# BMSnew.net
KiCad netlist of a schematic drawn in EAGLE
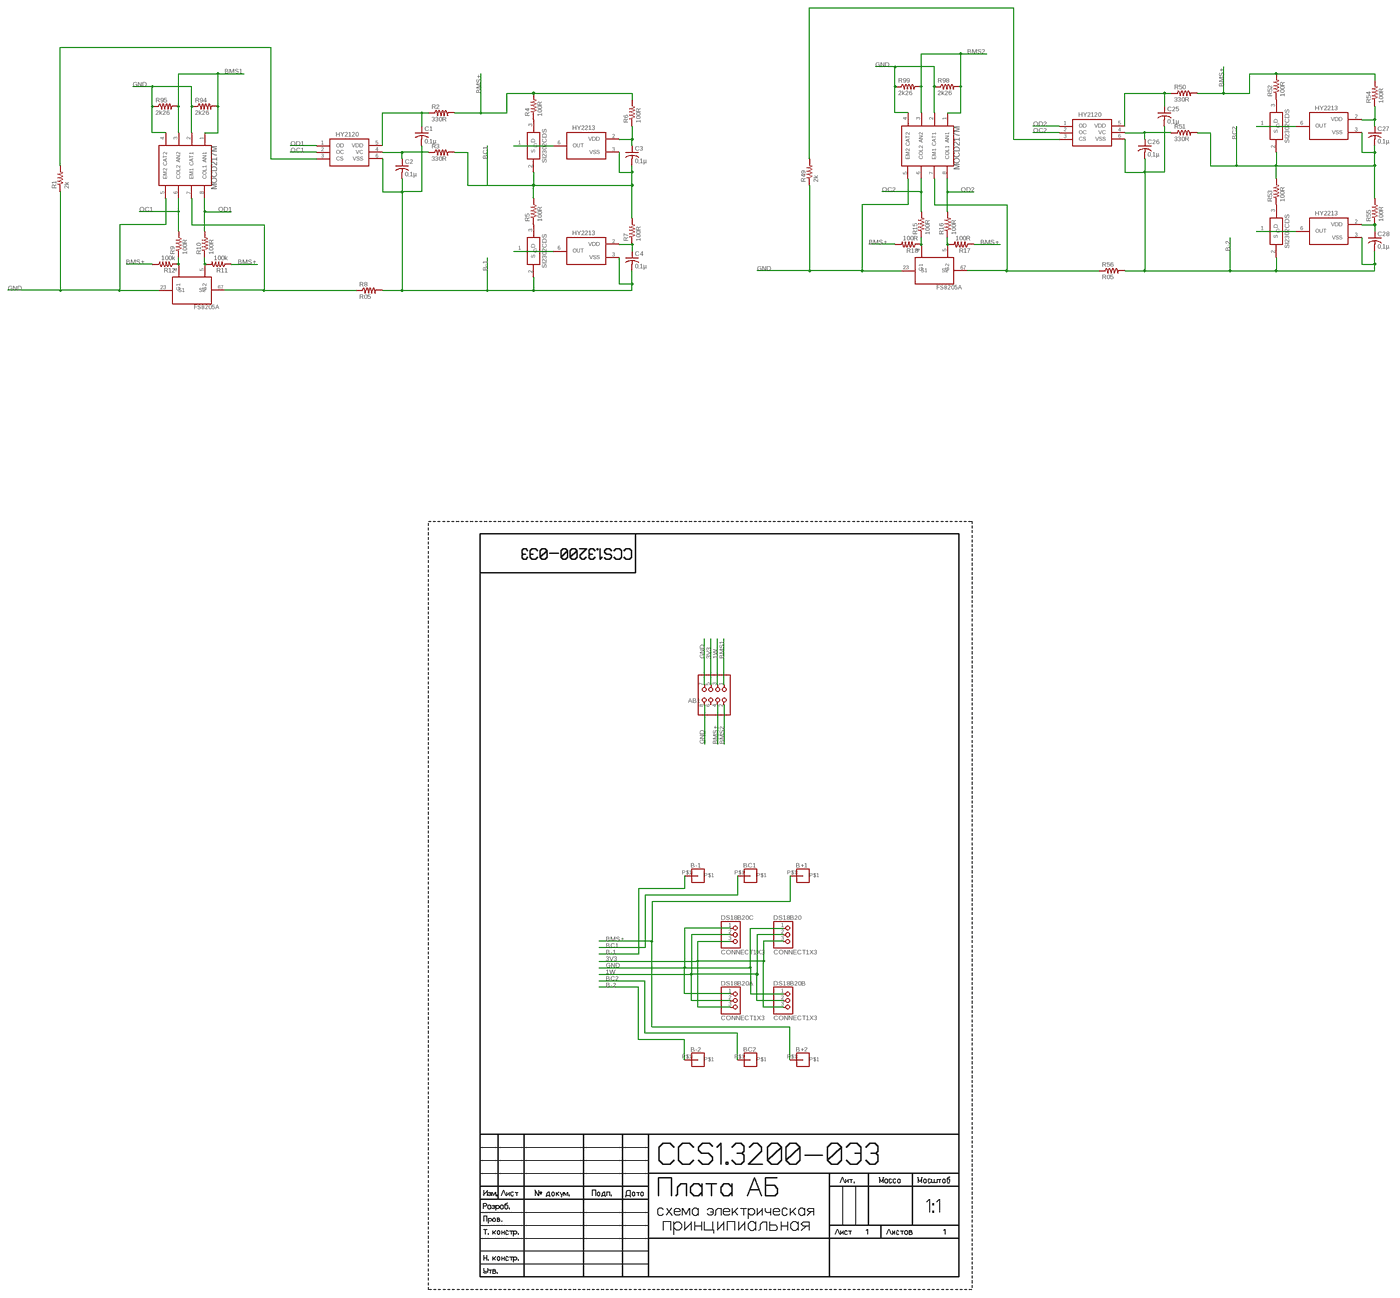
[diagram p0: schematic, sheet 1, overview]
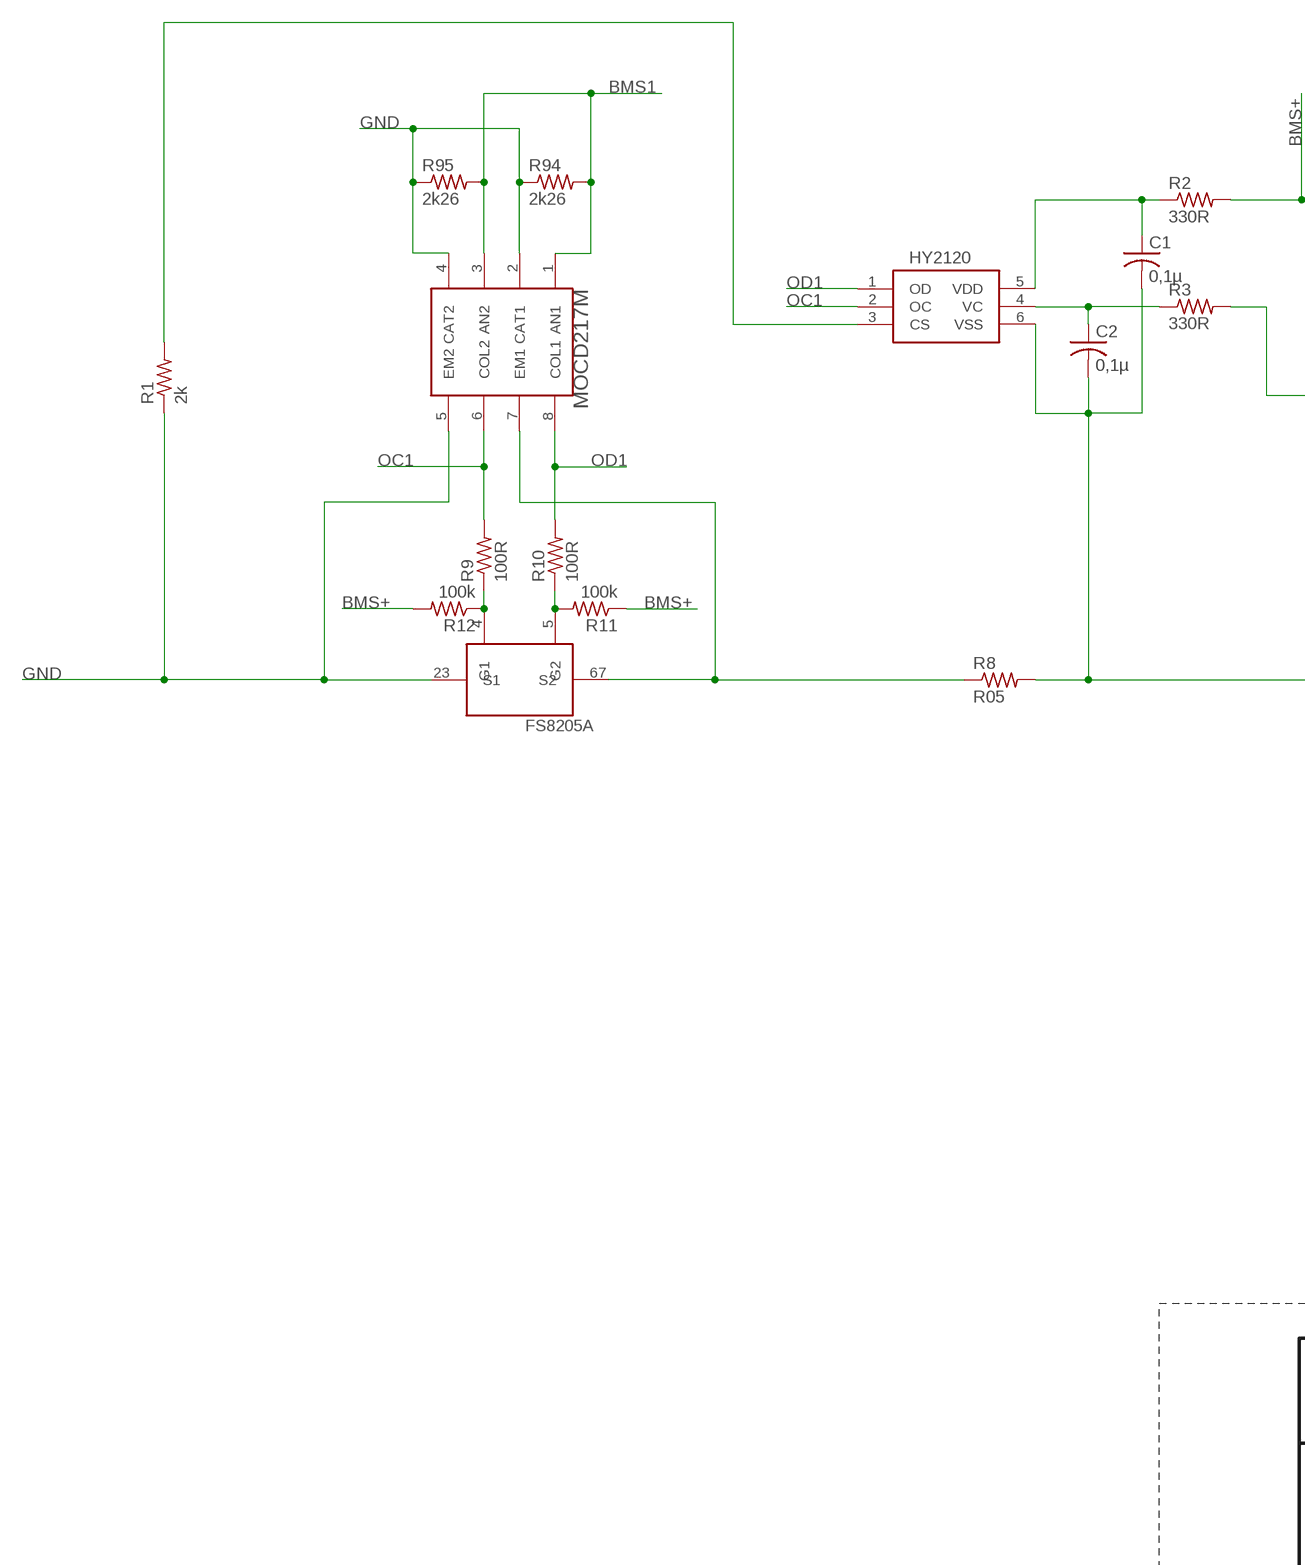
[diagram p1: schematic, sheet 1, part 1 of 4]
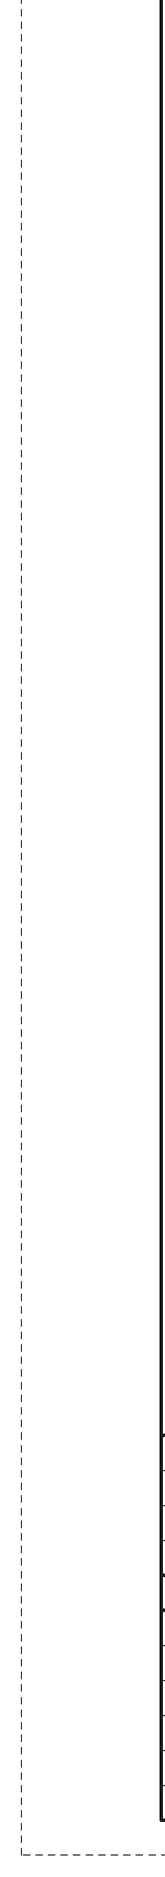
[diagram p2: schematic, sheet 1, part 2 of 4]
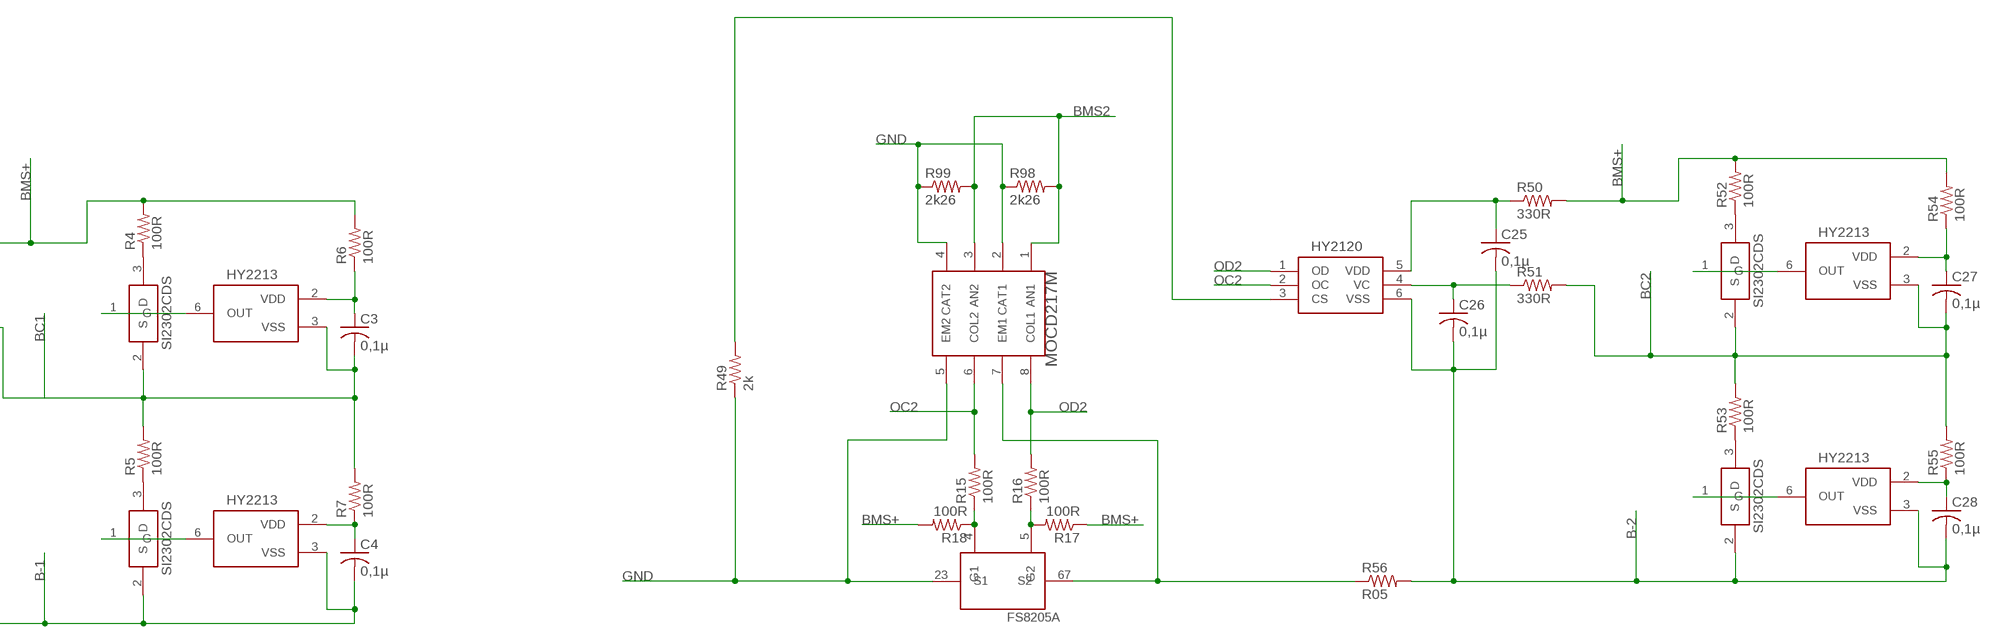
[diagram p3: schematic, sheet 1, part 3 of 4]
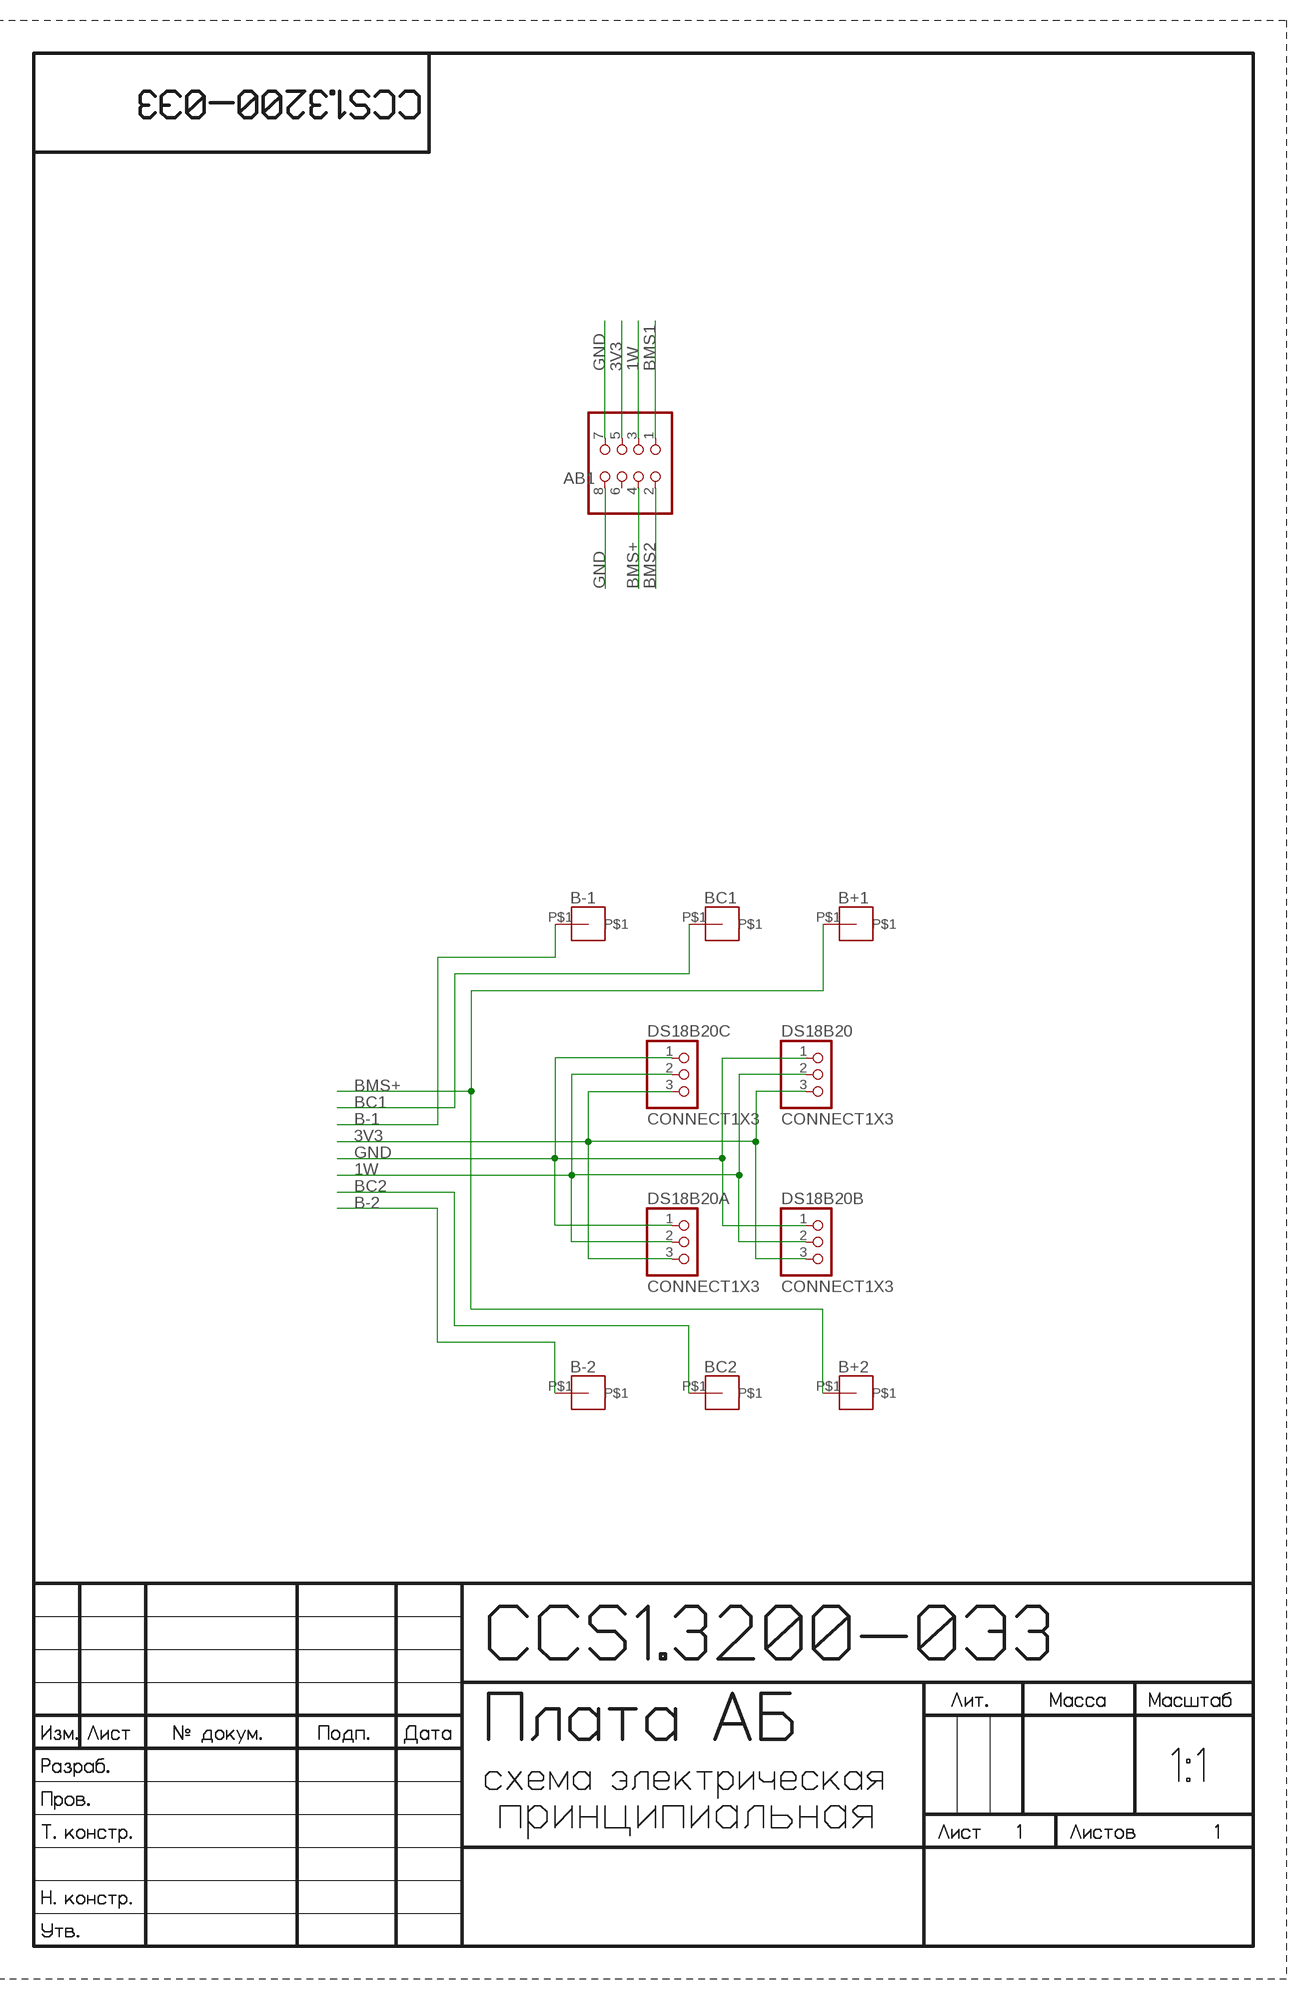
[diagram p4: schematic, sheet 1, part 4 of 4]

(export (version "E")
  (design (tool "Eeschema 10.0.6"))
  (components
    (comp (ref "AB1")
      (value "PINHD-2X4")
      (footprint "eagle-import:2X04")
      (libsource (lib "eagle-import") (part "PINHD-2X4"))
    )
    (comp (ref "B+1")
      (value "BATTERY")
      (footprint "eagle-import:BATTERY")
      (libsource (lib "eagle-import") (part "BATTERY"))
    )
    (comp (ref "B+2")
      (value "BATTERY")
      (footprint "eagle-import:BATTERY")
      (libsource (lib "eagle-import") (part "BATTERY"))
    )
    (comp (ref "B-1")
      (value "BATTERY")
      (footprint "eagle-import:BATTERY")
      (libsource (lib "eagle-import") (part "BATTERY"))
    )
    (comp (ref "B-2")
      (value "BATTERY")
      (footprint "eagle-import:BATTERY")
      (libsource (lib "eagle-import") (part "BATTERY"))
    )
    (comp (ref "BC1")
      (value "BATTERY")
      (footprint "eagle-import:BATTERY")
      (libsource (lib "eagle-import") (part "BATTERY"))
    )
    (comp (ref "BC2")
      (value "BATTERY")
      (footprint "eagle-import:BATTERY")
      (libsource (lib "eagle-import") (part "BATTERY"))
    )
    (comp (ref "C1")
      (value "0,1µ")
      (footprint "eagle-import:C0603")
      (libsource (lib "eagle-import") (part "C-USC0603"))
    )
    (comp (ref "C2")
      (value "0,1µ")
      (footprint "eagle-import:C0603")
      (libsource (lib "eagle-import") (part "C-USC0603"))
    )
    (comp (ref "C3")
      (value "0,1µ")
      (footprint "eagle-import:C0603")
      (libsource (lib "eagle-import") (part "C-USC0603"))
    )
    (comp (ref "C4")
      (value "0,1µ")
      (footprint "eagle-import:C0603")
      (libsource (lib "eagle-import") (part "C-USC0603"))
    )
    (comp (ref "C25")
      (value "0,1µ")
      (footprint "eagle-import:C0603")
      (libsource (lib "eagle-import") (part "C-USC0603"))
    )
    (comp (ref "C26")
      (value "0,1µ")
      (footprint "eagle-import:C0603")
      (libsource (lib "eagle-import") (part "C-USC0603"))
    )
    (comp (ref "C27")
      (value "0,1µ")
      (footprint "eagle-import:C0603")
      (libsource (lib "eagle-import") (part "C-USC0603"))
    )
    (comp (ref "C28")
      (value "0,1µ")
      (footprint "eagle-import:C0603")
      (libsource (lib "eagle-import") (part "C-USC0603"))
    )
    (comp (ref "DS18B20")
      (value "CONNECT1X3")
      (footprint "eagle-import:CONNECT1X3")
      (libsource (lib "eagle-import") (part "CONNECT1X3"))
    )
    (comp (ref "DS18B20A")
      (value "CONNECT1X3")
      (footprint "eagle-import:CONNECT1X3")
      (libsource (lib "eagle-import") (part "CONNECT1X3"))
    )
    (comp (ref "DS18B20B")
      (value "CONNECT1X3")
      (footprint "eagle-import:CONNECT1X3")
      (libsource (lib "eagle-import") (part "CONNECT1X3"))
    )
    (comp (ref "DS18B20C")
      (value "CONNECT1X3")
      (footprint "eagle-import:CONNECT1X3")
      (libsource (lib "eagle-import") (part "CONNECT1X3"))
    )
    (comp (ref "R1")
      (value "2k")
      (footprint "eagle-import:R0603")
      (libsource (lib "eagle-import") (part "resistor_348_R-US_R0603"))
    )
    (comp (ref "R2")
      (value "330R")
      (footprint "eagle-import:R0603")
      (libsource (lib "eagle-import") (part "resistor_348_R-US_R0603"))
    )
    (comp (ref "R3")
      (value "330R")
      (footprint "eagle-import:R0603")
      (libsource (lib "eagle-import") (part "resistor_348_R-US_R0603"))
    )
    (comp (ref "R4")
      (value "100R")
      (footprint "eagle-import:R0603")
      (libsource (lib "eagle-import") (part "resistor_348_R-US_R0603"))
    )
    (comp (ref "R5")
      (value "100R")
      (footprint "eagle-import:R0603")
      (libsource (lib "eagle-import") (part "resistor_348_R-US_R0603"))
    )
    (comp (ref "R6")
      (value "100R")
      (footprint "eagle-import:R0603")
      (libsource (lib "eagle-import") (part "resistor_348_R-US_R0603"))
    )
    (comp (ref "R7")
      (value "100R")
      (footprint "eagle-import:R0603")
      (libsource (lib "eagle-import") (part "resistor_348_R-US_R0603"))
    )
    (comp (ref "R8")
      (value "R05")
      (footprint "eagle-import:R2512")
      (libsource (lib "eagle-import") (part "R-US_R2512"))
    )
    (comp (ref "R9")
      (value "100R")
      (footprint "eagle-import:R0603")
      (libsource (lib "eagle-import") (part "resistor_348_R-US_R0603"))
    )
    (comp (ref "R10")
      (value "100R")
      (footprint "eagle-import:R0603")
      (libsource (lib "eagle-import") (part "resistor_348_R-US_R0603"))
    )
    (comp (ref "R11")
      (value "100k")
      (footprint "eagle-import:R0603")
      (libsource (lib "eagle-import") (part "resistor_348_R-US_R0603"))
    )
    (comp (ref "R12")
      (value "100k")
      (footprint "eagle-import:R0603")
      (libsource (lib "eagle-import") (part "resistor_348_R-US_R0603"))
    )
    (comp (ref "R15")
      (value "100R")
      (footprint "eagle-import:R0603")
      (libsource (lib "eagle-import") (part "resistor_348_R-US_R0603"))
    )
    (comp (ref "R16")
      (value "100R")
      (footprint "eagle-import:R0603")
      (libsource (lib "eagle-import") (part "resistor_348_R-US_R0603"))
    )
    (comp (ref "R17")
      (value "100R")
      (footprint "eagle-import:R0603")
      (libsource (lib "eagle-import") (part "resistor_348_R-US_R0603"))
    )
    (comp (ref "R18")
      (value "100R")
      (footprint "eagle-import:R0603")
      (libsource (lib "eagle-import") (part "resistor_348_R-US_R0603"))
    )
    (comp (ref "R49")
      (value "2k")
      (footprint "eagle-import:R0603")
      (libsource (lib "eagle-import") (part "resistor_348_R-US_R0603"))
    )
    (comp (ref "R50")
      (value "330R")
      (footprint "eagle-import:R0603")
      (libsource (lib "eagle-import") (part "resistor_348_R-US_R0603"))
    )
    (comp (ref "R51")
      (value "330R")
      (footprint "eagle-import:R0603")
      (libsource (lib "eagle-import") (part "resistor_348_R-US_R0603"))
    )
    (comp (ref "R52")
      (value "100R")
      (footprint "eagle-import:R0603")
      (libsource (lib "eagle-import") (part "resistor_348_R-US_R0603"))
    )
    (comp (ref "R53")
      (value "100R")
      (footprint "eagle-import:R0603")
      (libsource (lib "eagle-import") (part "resistor_348_R-US_R0603"))
    )
    (comp (ref "R54")
      (value "100R")
      (footprint "eagle-import:R0603")
      (libsource (lib "eagle-import") (part "resistor_348_R-US_R0603"))
    )
    (comp (ref "R55")
      (value "100R")
      (footprint "eagle-import:R0603")
      (libsource (lib "eagle-import") (part "resistor_348_R-US_R0603"))
    )
    (comp (ref "R56")
      (value "R05")
      (footprint "eagle-import:R2512")
      (libsource (lib "eagle-import") (part "R-US_R2512"))
    )
    (comp (ref "R94")
      (value "2k26")
      (footprint "eagle-import:R0603")
      (libsource (lib "eagle-import") (part "resistor_348_R-US_R0603"))
    )
    (comp (ref "R95")
      (value "2k26")
      (footprint "eagle-import:R0603")
      (libsource (lib "eagle-import") (part "resistor_348_R-US_R0603"))
    )
    (comp (ref "R98")
      (value "2k26")
      (footprint "eagle-import:R0603")
      (libsource (lib "eagle-import") (part "resistor_348_R-US_R0603"))
    )
    (comp (ref "R99")
      (value "2k26")
      (footprint "eagle-import:R0603")
      (libsource (lib "eagle-import") (part "resistor_348_R-US_R0603"))
    )
    (comp (ref "U$1")
      (value "FS8205A-")
      (footprint "eagle-import:FS8205A-")
      (libsource (lib "eagle-import") (part "FS8205A-"))
    )
    (comp (ref "U$2")
      (value "MOCD217M")
      (footprint "eagle-import:SOIC8")
      (libsource (lib "eagle-import") (part "MOCD217M"))
    )
    (comp (ref "U$3")
      (value "HY2120")
      (footprint "eagle-import:HY2120")
      (libsource (lib "eagle-import") (part "HY2120"))
    )
    (comp (ref "U$4")
      (value "HY2213")
      (footprint "eagle-import:HY2213")
      (libsource (lib "eagle-import") (part "HY2213"))
    )
    (comp (ref "U$5")
      (value "HY2213")
      (footprint "eagle-import:HY2213")
      (libsource (lib "eagle-import") (part "HY2213"))
    )
    (comp (ref "U$6")
      (value "SI2302CDS")
      (footprint "eagle-import:SI2302CDS")
      (libsource (lib "eagle-import") (part "SI2302CDS"))
    )
    (comp (ref "U$7")
      (value "SI2302CDS")
      (footprint "eagle-import:SI2302CDS")
      (libsource (lib "eagle-import") (part "SI2302CDS"))
    )
    (comp (ref "U$10")
      (value "MOCD217M")
      (footprint "eagle-import:SOIC8")
      (libsource (lib "eagle-import") (part "MOCD217M"))
    )
    (comp (ref "U$26")
      (value "FS8205A-")
      (footprint "eagle-import:FS8205A-")
      (libsource (lib "eagle-import") (part "FS8205A-"))
    )
    (comp (ref "U$45")
      (value "HY2120")
      (footprint "eagle-import:HY2120")
      (libsource (lib "eagle-import") (part "HY2120"))
    )
    (comp (ref "U$46")
      (value "HY2213")
      (footprint "eagle-import:HY2213")
      (libsource (lib "eagle-import") (part "HY2213"))
    )
    (comp (ref "U$47")
      (value "HY2213")
      (footprint "eagle-import:HY2213")
      (libsource (lib "eagle-import") (part "HY2213"))
    )
    (comp (ref "U$48")
      (value "SI2302CDS")
      (footprint "eagle-import:SI2302CDS")
      (libsource (lib "eagle-import") (part "SI2302CDS"))
    )
    (comp (ref "U$49")
      (value "SI2302CDS")
      (footprint "eagle-import:SI2302CDS")
      (libsource (lib "eagle-import") (part "SI2302CDS"))
    )
  )
  (nets
    (net (code "1") (name "/1W") (class "Default")
      (node (ref "AB1") (pin "3") (pinfunction "3_3") (pintype "passive"))
      (node (ref "DS18B20") (pin "2") (pinfunction "2_2") (pintype "passive"))
      (node (ref "DS18B20A") (pin "2") (pinfunction "2_2") (pintype "passive"))
      (node (ref "DS18B20B") (pin "2") (pinfunction "2_2") (pintype "passive"))
      (node (ref "DS18B20C") (pin "2") (pinfunction "2_2") (pintype "passive"))
    )
    (net (code "2") (name "/3V3") (class "Default")
      (node (ref "AB1") (pin "5") (pinfunction "5_5") (pintype "passive"))
      (node (ref "DS18B20") (pin "3") (pinfunction "3_3") (pintype "passive"))
      (node (ref "DS18B20A") (pin "3") (pinfunction "3_3") (pintype "passive"))
      (node (ref "DS18B20B") (pin "3") (pinfunction "3_3") (pintype "passive"))
      (node (ref "DS18B20C") (pin "3") (pinfunction "3_3") (pintype "passive"))
    )
    (net (code "3") (name "/B-1") (class "Default")
      (node (ref "B-1") (pin "P$1") (pinfunction "P$1_P$1") (pintype "bidirectional"))
      (node (ref "C1") (pin "2") (pinfunction "2_2") (pintype "passive"))
      (node (ref "C2") (pin "2") (pinfunction "2_2") (pintype "passive"))
      (node (ref "C4") (pin "2") (pinfunction "2_2") (pintype "passive"))
      (node (ref "R8") (pin "2") (pinfunction "2_2") (pintype "passive"))
      (node (ref "U$3") (pin "6") (pinfunction "VSS_6") (pintype "bidirectional"))
      (node (ref "U$5") (pin "3") (pinfunction "VSS_3") (pintype "bidirectional"))
      (node (ref "U$7") (pin "2") (pinfunction "S_2") (pintype "bidirectional"))
    )
    (net (code "4") (name "/B-2") (class "Default")
      (node (ref "B-2") (pin "P$1") (pinfunction "P$1_P$1") (pintype "bidirectional"))
      (node (ref "C25") (pin "2") (pinfunction "2_2") (pintype "passive"))
      (node (ref "C26") (pin "2") (pinfunction "2_2") (pintype "passive"))
      (node (ref "C28") (pin "2") (pinfunction "2_2") (pintype "passive"))
      (node (ref "R56") (pin "2") (pinfunction "2_2") (pintype "passive"))
      (node (ref "U$45") (pin "6") (pinfunction "VSS_6") (pintype "bidirectional"))
      (node (ref "U$47") (pin "3") (pinfunction "VSS_3") (pintype "bidirectional"))
      (node (ref "U$49") (pin "2") (pinfunction "S_2") (pintype "bidirectional"))
    )
    (net (code "5") (name "/BC1") (class "Default")
      (node (ref "BC1") (pin "P$1") (pinfunction "P$1_P$1") (pintype "bidirectional"))
      (node (ref "C3") (pin "2") (pinfunction "2_2") (pintype "passive"))
      (node (ref "R3") (pin "2") (pinfunction "2_2") (pintype "passive"))
      (node (ref "R5") (pin "2") (pinfunction "2_2") (pintype "passive"))
      (node (ref "R7") (pin "2") (pinfunction "2_2") (pintype "passive"))
      (node (ref "U$4") (pin "3") (pinfunction "VSS_3") (pintype "bidirectional"))
      (node (ref "U$6") (pin "2") (pinfunction "S_2") (pintype "bidirectional"))
    )
    (net (code "6") (name "/BC2") (class "Default")
      (node (ref "BC2") (pin "P$1") (pinfunction "P$1_P$1") (pintype "bidirectional"))
      (node (ref "C27") (pin "2") (pinfunction "2_2") (pintype "passive"))
      (node (ref "R51") (pin "2") (pinfunction "2_2") (pintype "passive"))
      (node (ref "R53") (pin "2") (pinfunction "2_2") (pintype "passive"))
      (node (ref "R55") (pin "2") (pinfunction "2_2") (pintype "passive"))
      (node (ref "U$46") (pin "3") (pinfunction "VSS_3") (pintype "bidirectional"))
      (node (ref "U$48") (pin "2") (pinfunction "S_2") (pintype "bidirectional"))
    )
    (net (code "7") (name "/BMS+") (class "Default")
      (node (ref "AB1") (pin "4") (pinfunction "4_4") (pintype "passive"))
      (node (ref "B+1") (pin "P$1") (pinfunction "P$1_P$1") (pintype "bidirectional"))
      (node (ref "B+2") (pin "P$1") (pinfunction "P$1_P$1") (pintype "bidirectional"))
      (node (ref "R11") (pin "1") (pinfunction "1_1") (pintype "passive"))
      (node (ref "R12") (pin "2") (pinfunction "2_2") (pintype "passive"))
      (node (ref "R17") (pin "1") (pinfunction "1_1") (pintype "passive"))
      (node (ref "R18") (pin "2") (pinfunction "2_2") (pintype "passive"))
      (node (ref "R2") (pin "2") (pinfunction "2_2") (pintype "passive"))
      (node (ref "R4") (pin "2") (pinfunction "2_2") (pintype "passive"))
      (node (ref "R50") (pin "2") (pinfunction "2_2") (pintype "passive"))
      (node (ref "R52") (pin "2") (pinfunction "2_2") (pintype "passive"))
      (node (ref "R54") (pin "2") (pinfunction "2_2") (pintype "passive"))
      (node (ref "R6") (pin "2") (pinfunction "2_2") (pintype "passive"))
    )
    (net (code "8") (name "/BMS1") (class "Default")
      (node (ref "AB1") (pin "1") (pinfunction "1_1") (pintype "passive"))
      (node (ref "R94") (pin "2") (pinfunction "2_2") (pintype "passive"))
      (node (ref "R95") (pin "2") (pinfunction "2_2") (pintype "passive"))
      (node (ref "U$2") (pin "1") (pinfunction "AN1_1") (pintype "bidirectional"))
      (node (ref "U$2") (pin "3") (pinfunction "AN2_3") (pintype "bidirectional"))
    )
    (net (code "9") (name "/BMS2") (class "Default")
      (node (ref "AB1") (pin "2") (pinfunction "2_2") (pintype "passive"))
      (node (ref "R98") (pin "2") (pinfunction "2_2") (pintype "passive"))
      (node (ref "R99") (pin "2") (pinfunction "2_2") (pintype "passive"))
      (node (ref "U$10") (pin "1") (pinfunction "AN1_1") (pintype "bidirectional"))
      (node (ref "U$10") (pin "3") (pinfunction "AN2_3") (pintype "bidirectional"))
    )
    (net (code "10") (name "/GND") (class "Default")
      (node (ref "AB1") (pin "7") (pinfunction "7_7") (pintype "passive"))
      (node (ref "AB1") (pin "8") (pinfunction "8_8") (pintype "passive"))
      (node (ref "DS18B20") (pin "1") (pinfunction "1_1") (pintype "passive"))
      (node (ref "DS18B20A") (pin "1") (pinfunction "1_1") (pintype "passive"))
      (node (ref "DS18B20B") (pin "1") (pinfunction "1_1") (pintype "passive"))
      (node (ref "DS18B20C") (pin "1") (pinfunction "1_1") (pintype "passive"))
      (node (ref "R1") (pin "1") (pinfunction "1_1") (pintype "passive"))
      (node (ref "R49") (pin "1") (pinfunction "1_1") (pintype "passive"))
      (node (ref "R94") (pin "1") (pinfunction "1_1") (pintype "passive"))
      (node (ref "R95") (pin "1") (pinfunction "1_1") (pintype "passive"))
      (node (ref "R98") (pin "1") (pinfunction "1_1") (pintype "passive"))
      (node (ref "R99") (pin "1") (pinfunction "1_1") (pintype "passive"))
      (node (ref "U$1") (pin "23") (pinfunction "S1_23") (pintype "bidirectional"))
      (node (ref "U$10") (pin "2") (pinfunction "CAT1_2") (pintype "bidirectional"))
      (node (ref "U$10") (pin "4") (pinfunction "CAT2_4") (pintype "bidirectional"))
      (node (ref "U$10") (pin "5") (pinfunction "EM2_5") (pintype "bidirectional"))
      (node (ref "U$2") (pin "2") (pinfunction "CAT1_2") (pintype "bidirectional"))
      (node (ref "U$2") (pin "4") (pinfunction "CAT2_4") (pintype "bidirectional"))
      (node (ref "U$2") (pin "5") (pinfunction "EM2_5") (pintype "bidirectional"))
      (node (ref "U$26") (pin "23") (pinfunction "S1_23") (pintype "bidirectional"))
    )
    (net (code "11") (name "/OC1") (class "Default")
      (node (ref "R9") (pin "2") (pinfunction "2_2") (pintype "passive"))
      (node (ref "U$2") (pin "6") (pinfunction "COL2_6") (pintype "bidirectional"))
      (node (ref "U$3") (pin "2") (pinfunction "OC_2") (pintype "bidirectional"))
    )
    (net (code "12") (name "/OC2") (class "Default")
      (node (ref "R15") (pin "2") (pinfunction "2_2") (pintype "passive"))
      (node (ref "U$10") (pin "6") (pinfunction "COL2_6") (pintype "bidirectional"))
      (node (ref "U$45") (pin "2") (pinfunction "OC_2") (pintype "bidirectional"))
    )
    (net (code "13") (name "/OD1") (class "Default")
      (node (ref "R10") (pin "2") (pinfunction "2_2") (pintype "passive"))
      (node (ref "U$2") (pin "8") (pinfunction "COL1_8") (pintype "bidirectional"))
      (node (ref "U$3") (pin "1") (pinfunction "OD_1") (pintype "bidirectional"))
    )
    (net (code "14") (name "/OD2") (class "Default")
      (node (ref "R16") (pin "2") (pinfunction "2_2") (pintype "passive"))
      (node (ref "U$10") (pin "8") (pinfunction "COL1_8") (pintype "bidirectional"))
      (node (ref "U$45") (pin "1") (pinfunction "OD_1") (pintype "bidirectional"))
    )
    (net (code "15") (name "Net-(U$1-G1)") (class "Default")
      (node (ref "R15") (pin "1") (pinfunction "1_1") (pintype "passive"))
      (node (ref "R18") (pin "1") (pinfunction "1_1") (pintype "passive"))
      (node (ref "U$1") (pin "4") (pinfunction "G1_4") (pintype "bidirectional"))
    )
    (net (code "16") (name "Net-(U$1-G2)") (class "Default")
      (node (ref "R16") (pin "1") (pinfunction "1_1") (pintype "passive"))
      (node (ref "R17") (pin "2") (pinfunction "2_2") (pintype "passive"))
      (node (ref "U$1") (pin "5") (pinfunction "G2_5") (pintype "bidirectional"))
    )
    (net (code "17") (name "Net-(U$1-S2)") (class "Default")
      (node (ref "R56") (pin "1") (pinfunction "1_1") (pintype "passive"))
      (node (ref "U$1") (pin "67") (pinfunction "S2_67") (pintype "bidirectional"))
      (node (ref "U$10") (pin "7") (pinfunction "EM1_7") (pintype "bidirectional"))
    )
    (net (code "18") (name "Net-(U$2-EM1)") (class "Default")
      (node (ref "R8") (pin "1") (pinfunction "1_1") (pintype "passive"))
      (node (ref "U$2") (pin "7") (pinfunction "EM1_7") (pintype "bidirectional"))
      (node (ref "U$26") (pin "67") (pinfunction "S2_67") (pintype "bidirectional"))
    )
    (net (code "19") (name "Net-(U$3-CS)") (class "Default")
      (node (ref "R1") (pin "2") (pinfunction "2_2") (pintype "passive"))
      (node (ref "U$3") (pin "3") (pinfunction "CS_3") (pintype "bidirectional"))
    )
    (net (code "20") (name "Net-(U$3-VC)") (class "Default")
      (node (ref "C2") (pin "1") (pinfunction "1_1") (pintype "passive"))
      (node (ref "R3") (pin "1") (pinfunction "1_1") (pintype "passive"))
      (node (ref "U$3") (pin "4") (pinfunction "VC_4") (pintype "bidirectional"))
    )
    (net (code "21") (name "Net-(U$3-VDD)") (class "Default")
      (node (ref "C1") (pin "1") (pinfunction "1_1") (pintype "passive"))
      (node (ref "R2") (pin "1") (pinfunction "1_1") (pintype "passive"))
      (node (ref "U$3") (pin "5") (pinfunction "VDD_5") (pintype "bidirectional"))
    )
    (net (code "22") (name "Net-(U$4-OUT)") (class "Default")
      (node (ref "U$4") (pin "6") (pinfunction "OUT_6") (pintype "bidirectional"))
      (node (ref "U$6") (pin "1") (pinfunction "G_1") (pintype "bidirectional"))
    )
    (net (code "23") (name "Net-(U$4-VDD)") (class "Default")
      (node (ref "C3") (pin "1") (pinfunction "1_1") (pintype "passive"))
      (node (ref "R6") (pin "1") (pinfunction "1_1") (pintype "passive"))
      (node (ref "U$4") (pin "2") (pinfunction "VDD_2") (pintype "bidirectional"))
    )
    (net (code "24") (name "Net-(U$5-OUT)") (class "Default")
      (node (ref "U$5") (pin "6") (pinfunction "OUT_6") (pintype "bidirectional"))
      (node (ref "U$7") (pin "1") (pinfunction "G_1") (pintype "bidirectional"))
    )
    (net (code "25") (name "Net-(U$5-VDD)") (class "Default")
      (node (ref "C4") (pin "1") (pinfunction "1_1") (pintype "passive"))
      (node (ref "R7") (pin "1") (pinfunction "1_1") (pintype "passive"))
      (node (ref "U$5") (pin "2") (pinfunction "VDD_2") (pintype "bidirectional"))
    )
    (net (code "26") (name "Net-(U$6-D)") (class "Default")
      (node (ref "R4") (pin "1") (pinfunction "1_1") (pintype "passive"))
      (node (ref "U$6") (pin "3") (pinfunction "D_3") (pintype "bidirectional"))
    )
    (net (code "27") (name "Net-(U$7-D)") (class "Default")
      (node (ref "R5") (pin "1") (pinfunction "1_1") (pintype "passive"))
      (node (ref "U$7") (pin "3") (pinfunction "D_3") (pintype "bidirectional"))
    )
    (net (code "28") (name "Net-(U$26-G1)") (class "Default")
      (node (ref "R12") (pin "1") (pinfunction "1_1") (pintype "passive"))
      (node (ref "R9") (pin "1") (pinfunction "1_1") (pintype "passive"))
      (node (ref "U$26") (pin "4") (pinfunction "G1_4") (pintype "bidirectional"))
    )
    (net (code "29") (name "Net-(U$26-G2)") (class "Default")
      (node (ref "R10") (pin "1") (pinfunction "1_1") (pintype "passive"))
      (node (ref "R11") (pin "2") (pinfunction "2_2") (pintype "passive"))
      (node (ref "U$26") (pin "5") (pinfunction "G2_5") (pintype "bidirectional"))
    )
    (net (code "30") (name "Net-(U$45-CS)") (class "Default")
      (node (ref "R49") (pin "2") (pinfunction "2_2") (pintype "passive"))
      (node (ref "U$45") (pin "3") (pinfunction "CS_3") (pintype "bidirectional"))
    )
    (net (code "31") (name "Net-(U$45-VC)") (class "Default")
      (node (ref "C26") (pin "1") (pinfunction "1_1") (pintype "passive"))
      (node (ref "R51") (pin "1") (pinfunction "1_1") (pintype "passive"))
      (node (ref "U$45") (pin "4") (pinfunction "VC_4") (pintype "bidirectional"))
    )
    (net (code "32") (name "Net-(U$45-VDD)") (class "Default")
      (node (ref "C25") (pin "1") (pinfunction "1_1") (pintype "passive"))
      (node (ref "R50") (pin "1") (pinfunction "1_1") (pintype "passive"))
      (node (ref "U$45") (pin "5") (pinfunction "VDD_5") (pintype "bidirectional"))
    )
    (net (code "33") (name "Net-(U$46-OUT)") (class "Default")
      (node (ref "U$46") (pin "6") (pinfunction "OUT_6") (pintype "bidirectional"))
      (node (ref "U$48") (pin "1") (pinfunction "G_1") (pintype "bidirectional"))
    )
    (net (code "34") (name "Net-(U$46-VDD)") (class "Default")
      (node (ref "C27") (pin "1") (pinfunction "1_1") (pintype "passive"))
      (node (ref "R54") (pin "1") (pinfunction "1_1") (pintype "passive"))
      (node (ref "U$46") (pin "2") (pinfunction "VDD_2") (pintype "bidirectional"))
    )
    (net (code "35") (name "Net-(U$47-OUT)") (class "Default")
      (node (ref "U$47") (pin "6") (pinfunction "OUT_6") (pintype "bidirectional"))
      (node (ref "U$49") (pin "1") (pinfunction "G_1") (pintype "bidirectional"))
    )
    (net (code "36") (name "Net-(U$47-VDD)") (class "Default")
      (node (ref "C28") (pin "1") (pinfunction "1_1") (pintype "passive"))
      (node (ref "R55") (pin "1") (pinfunction "1_1") (pintype "passive"))
      (node (ref "U$47") (pin "2") (pinfunction "VDD_2") (pintype "bidirectional"))
    )
    (net (code "37") (name "Net-(U$48-D)") (class "Default")
      (node (ref "R52") (pin "1") (pinfunction "1_1") (pintype "passive"))
      (node (ref "U$48") (pin "3") (pinfunction "D_3") (pintype "bidirectional"))
    )
    (net (code "38") (name "Net-(U$49-D)") (class "Default")
      (node (ref "R53") (pin "1") (pinfunction "1_1") (pintype "passive"))
      (node (ref "U$49") (pin "3") (pinfunction "D_3") (pintype "bidirectional"))
    )
    (net (code "39") (name "unconnected-(AB1-Pad6)") (class "Default")
      (node (ref "AB1") (pin "6") (pinfunction "6_6") (pintype "passive"))
    )
  )
)
